# 4fader_main.net
KiCad netlist of a schematic drawn in Altium Designer
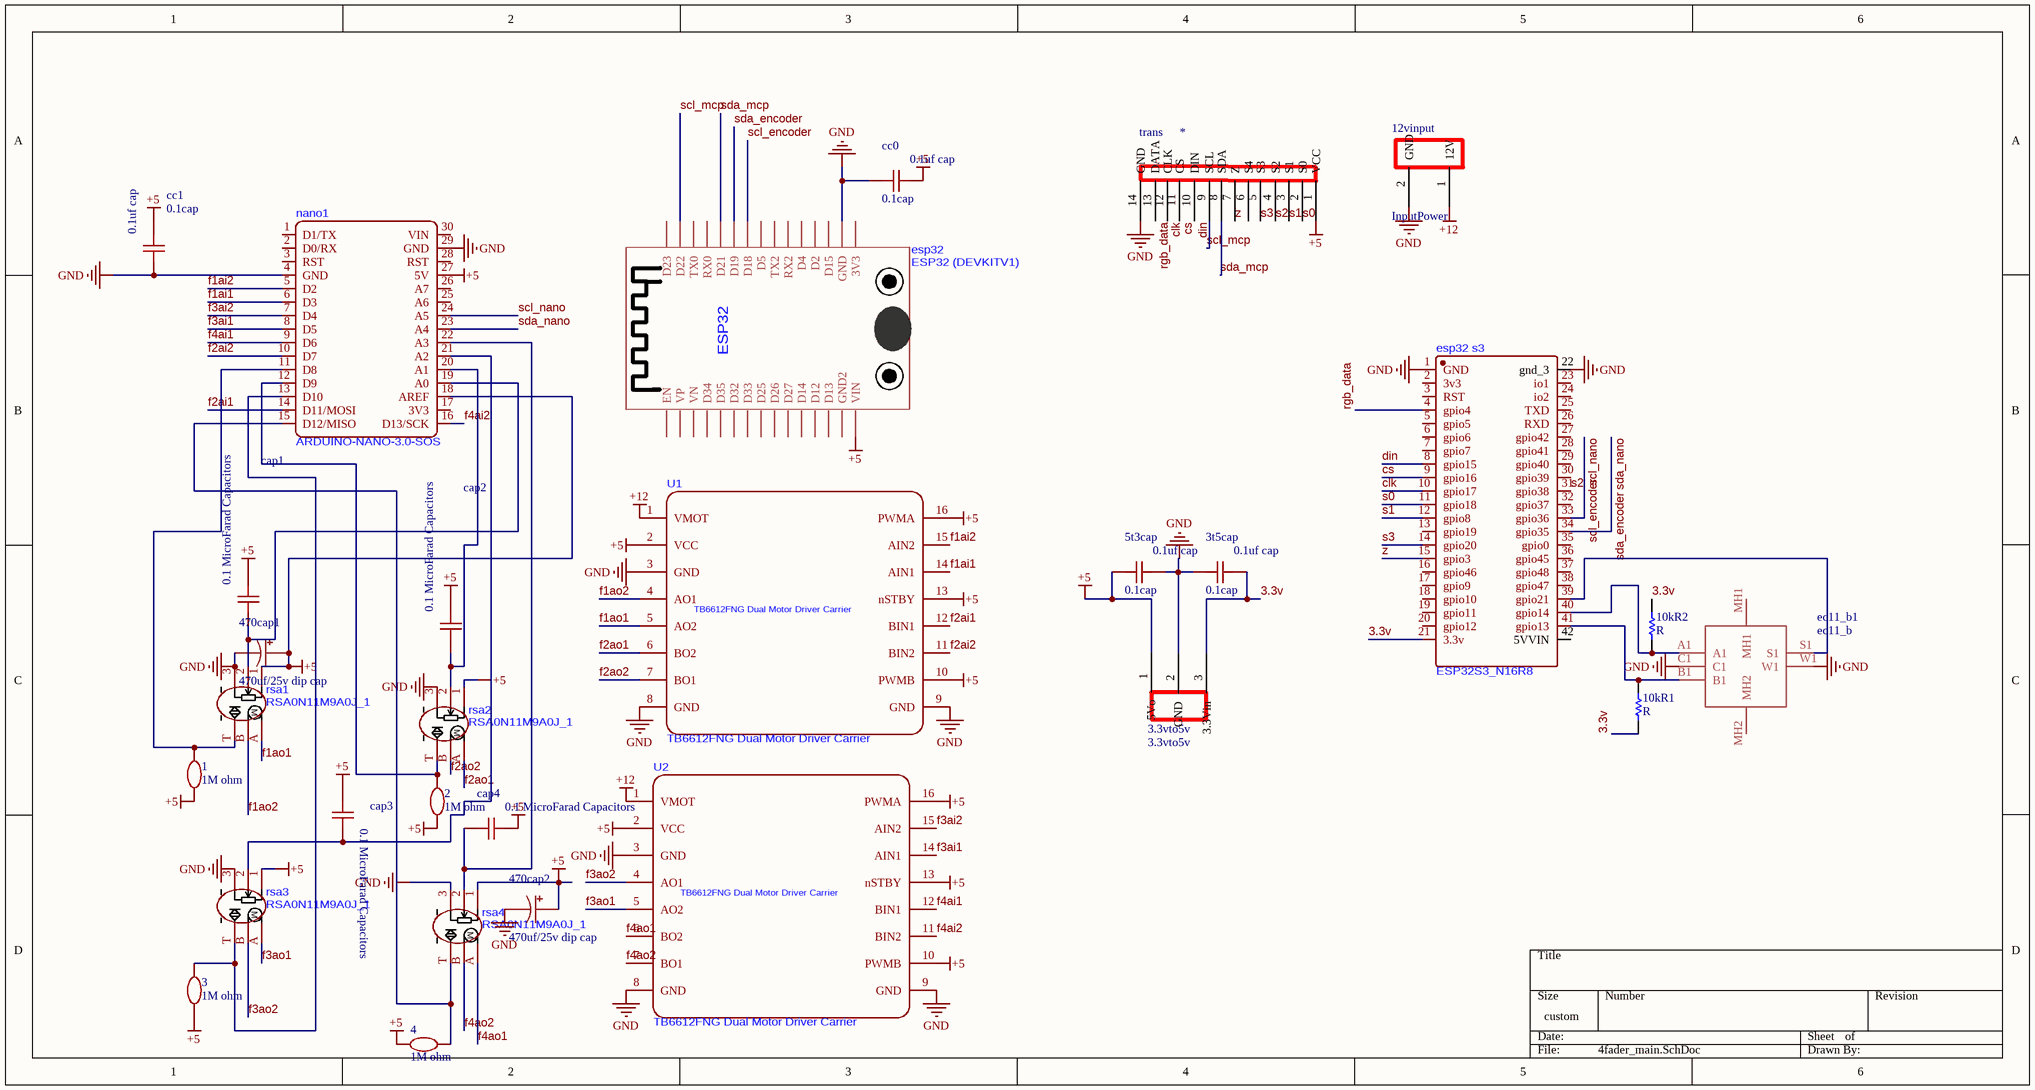
[diagram p0: 4fader_main.SchDoc]

(export (version "E")
  (design (tool "Eeschema 10.0.6"))
  (components
    (comp (ref "*")
      (value "trans")
      (footprint "FPC-SMD_KH-FG1.0-H2.0-14PIN")
      (libsource (lib "8_1") (part "trans"))
    )
    (comp (ref "1") (value "1M ohm") (footprint "ohms") (libsource (lib "8_1") (part "33k ohm")))
    (comp (ref "2") (value "1M ohm") (footprint "ohms") (libsource (lib "8_1") (part "33k ohm")))
    (comp (ref "3") (value "1M ohm") (footprint "ohms") (libsource (lib "8_1") (part "33k ohm")))
    (comp (ref "3.3vto5v")
      (value "3.3vto5v")
      (footprint "3.3vto5v")
      (libsource (lib "8_1") (part "3.3vto5v"))
    )
    (comp (ref "3t5cap") (value "0.1cap") (footprint "capcitor_1nf") (libsource (lib "8_1") (part "0.1cap")))
    (comp (ref "4") (value "1M ohm") (footprint "ohms") (libsource (lib "8_1") (part "33k ohm")))
    (comp (ref "5t3cap") (value "0.1cap") (footprint "capcitor_1nf") (libsource (lib "8_1") (part "0.1cap")))
    (comp (ref "10kR1")
      (value "R")
      (footprint "RESC2013X60X30LL20T20")
      (fields (field (name "MANUFACTURER") "KOA Speer") (field (name "PART NUMBER") "SG73S2ATTD1101F"))
      (libsource (lib "8_1") (part "CMP-2001-02660-1"))
    )
    (comp (ref "10kR2")
      (value "R")
      (footprint "RESC2013X60X30LL20T20")
      (fields (field (name "MANUFACTURER") "KOA Speer") (field (name "PART NUMBER") "SG73S2ATTD1101F"))
      (libsource (lib "8_1") (part "CMP-2001-02660-1"))
    )
    (comp (ref "12vinput")
      (value "InputPower")
      (footprint "InputPower")
      (libsource (lib "8_1") (part "InputPower"))
    )
    (comp (ref "470cap1")
      (value "470uf/25v dip cap")
      (footprint "470UF/25V-G1")
      (libsource (lib "8_1") (part "470uf/25v dip cap"))
    )
    (comp (ref "470cap2")
      (value "470uf/25v dip cap")
      (footprint "470UF/25V-G1")
      (libsource (lib "8_1") (part "470uf/25v dip cap"))
    )
    (comp (ref "cap1") (value "~") (footprint "capcitor_1nf") (libsource (lib "8_1") (part "0.1cap")))
    (comp (ref "cap2") (value "~") (footprint "capcitor_1nf") (libsource (lib "8_1") (part "0.1cap")))
    (comp (ref "cap3") (value "~") (footprint "capcitor_1nf") (libsource (lib "8_1") (part "0.1cap")))
    (comp (ref "cap4") (value "~") (footprint "capcitor_1nf") (libsource (lib "8_1") (part "0.1cap")))
    (comp (ref "cc0") (value "0.1cap") (footprint "capcitor_1nf") (libsource (lib "8_1") (part "0.1cap")))
    (comp (ref "cc1") (value "0.1cap") (footprint "capcitor_1nf") (libsource (lib "8_1") (part "0.1cap")))
    (comp (ref "ec11_b1") (value "ec11_b") (footprint "ec11_b") (libsource (lib "8_1") (part "ec11_b")))
    (comp (ref "esp32")
      (value "ESP32 (DEVKITV1)")
      (footprint "ESP32-DEVKITV1_ESP32-DEVKITV1")
      (libsource (lib "8_1") (part "ESP32 (DEVKITV1)"))
    )
    (comp (ref "esp32 s3")
      (value "ESP32S3_N16R8")
      (footprint "ESP32 S3 N16R8")
      (libsource (lib "8_1") (part "ESP32S3_N16R8"))
    )
    (comp (ref "nano1")
      (value "ARDUINO-NANO-3.0-SOS")
      (footprint "arduino_nano")
      (libsource (lib "8_1") (part "ARDUINO-NANO-3.0-SOS"))
    )
    (comp (ref "rsa1")
      (value "RSA0N11M9A0J_1")
      (footprint "RSA0N11M9A0J")
      (libsource (lib "8_1") (part "RSA0N11M9A0J_1"))
    )
    (comp (ref "rsa2")
      (value "RSA0N11M9A0J_1")
      (footprint "RSA0N11M9A0J")
      (libsource (lib "8_1") (part "RSA0N11M9A0J_1"))
    )
    (comp (ref "rsa3")
      (value "RSA0N11M9A0J_1")
      (footprint "RSA0N11M9A0J")
      (libsource (lib "8_1") (part "RSA0N11M9A0J_1"))
    )
    (comp (ref "rsa4")
      (value "RSA0N11M9A0J_1")
      (footprint "RSA0N11M9A0J")
      (libsource (lib "8_1") (part "RSA0N11M9A0J_1"))
    )
    (comp (ref "U1")
      (value "TB6612FNG Dual Motor Driver Carrier")
      (footprint "TB6612FNG")
      (libsource (lib "8_1") (part "TB6612FNG Dual Motor Driver Carrier"))
    )
    (comp (ref "U2")
      (value "TB6612FNG Dual Motor Driver Carrier")
      (footprint "TB6612FNG")
      (libsource (lib "8_1") (part "TB6612FNG Dual Motor Driver Carrier"))
    )
  )
  (nets
    (net (code "1") (name "+5") (class "Default")
      (node (ref "*") (pin "1") (pinfunction "VCC_1") (pintype "passive"))
      (node (ref "1") (pin "1") (pinfunction "1_1") (pintype "passive"))
      (node (ref "2") (pin "1") (pinfunction "1_1") (pintype "passive"))
      (node (ref "3") (pin "2") (pinfunction "2_2") (pintype "passive"))
      (node (ref "3.3vto5v") (pin "1") (pinfunction "5Vo_1") (pintype "passive"))
      (node (ref "4") (pin "2") (pinfunction "2_2") (pintype "passive"))
      (node (ref "470cap1") (pin "1") (pinfunction "1_1") (pintype "passive"))
      (node (ref "470cap2") (pin "1") (pinfunction "1_1") (pintype "passive"))
      (node (ref "5t3cap") (pin "1") (pinfunction "1_1") (pintype "passive"))
      (node (ref "U1") (pin "10") (pinfunction "PWMB_10") (pintype "passive"))
      (node (ref "U1") (pin "13") (pinfunction "nSTBY_13") (pintype "passive"))
      (node (ref "U1") (pin "16") (pinfunction "PWMA_16") (pintype "passive"))
      (node (ref "U1") (pin "2") (pinfunction "VCC_2") (pintype "passive"))
      (node (ref "U2") (pin "10") (pinfunction "PWMB_10") (pintype "passive"))
      (node (ref "U2") (pin "13") (pinfunction "nSTBY_13") (pintype "passive"))
      (node (ref "U2") (pin "16") (pinfunction "PWMA_16") (pintype "passive"))
      (node (ref "U2") (pin "2") (pinfunction "VCC_2") (pintype "passive"))
      (node (ref "cap1") (pin "2") (pinfunction "2_2") (pintype "passive"))
      (node (ref "cap2") (pin "2") (pinfunction "2_2") (pintype "passive"))
      (node (ref "cap3") (pin "1") (pinfunction "1_1") (pintype "passive"))
      (node (ref "cap4") (pin "2") (pinfunction "2_2") (pintype "passive"))
      (node (ref "cc0") (pin "2") (pinfunction "2_2") (pintype "passive"))
      (node (ref "cc1") (pin "2") (pinfunction "2_2") (pintype "passive"))
      (node (ref "esp32") (pin "VIN") (pinfunction "VIN_VIN") (pintype "passive"))
      (node (ref "nano1") (pin "18") (pinfunction "AREF_18") (pintype "passive"))
      (node (ref "nano1") (pin "27") (pinfunction "5V_27") (pintype "passive"))
      (node (ref "rsa1") (pin "1") (pinfunction "1_1") (pintype "passive"))
      (node (ref "rsa2") (pin "1") (pinfunction "1_1") (pintype "passive"))
      (node (ref "rsa3") (pin "1") (pinfunction "1_1") (pintype "passive"))
      (node (ref "rsa4") (pin "1") (pinfunction "1_1") (pintype "passive"))
    )
    (net (code "2") (name "+12") (class "Default")
      (node (ref "12vinput") (pin "1") (pinfunction "12V_1") (pintype "passive"))
      (node (ref "U1") (pin "1") (pinfunction "VMOT_1") (pintype "passive"))
      (node (ref "U2") (pin "1") (pinfunction "VMOT_1") (pintype "passive"))
    )
    (net (code "3") (name "/3.3v") (class "Default")
      (node (ref "10kR1") (pin "1") (pinfunction "1_1") (pintype "passive"))
      (node (ref "10kR2") (pin "2") (pinfunction "2_2") (pintype "passive"))
      (node (ref "3.3vto5v") (pin "3") (pinfunction "3.3Vin_3") (pintype "passive"))
      (node (ref "3t5cap") (pin "2") (pinfunction "2_2") (pintype "passive"))
      (node (ref "esp32 s3") (pin "21") (pinfunction "3.3v_21") (pintype "passive"))
    )
    (net (code "4") (name "/clk") (class "Default")
      (node (ref "*") (pin "12") (pinfunction "CLK_12") (pintype "passive"))
      (node (ref "esp32 s3") (pin "10") (pinfunction "gpio17_10") (pintype "passive"))
    )
    (net (code "5") (name "/cs") (class "Default")
      (node (ref "*") (pin "11") (pinfunction "CS_11") (pintype "passive"))
      (node (ref "esp32 s3") (pin "9") (pinfunction "gpio16_9") (pintype "passive"))
    )
    (net (code "6") (name "/din") (class "Default")
      (node (ref "*") (pin "10") (pinfunction "DIN_10") (pintype "passive"))
      (node (ref "esp32 s3") (pin "8") (pinfunction "gpio15_8") (pintype "passive"))
    )
    (net (code "7") (name "/f1ai1") (class "Default")
      (node (ref "U1") (pin "14") (pinfunction "AIN1_14") (pintype "passive"))
      (node (ref "nano1") (pin "6") (pinfunction "D3_6") (pintype "passive"))
    )
    (net (code "8") (name "/f1ai2") (class "Default")
      (node (ref "U1") (pin "15") (pinfunction "AIN2_15") (pintype "passive"))
      (node (ref "nano1") (pin "5") (pinfunction "D2_5") (pintype "passive"))
    )
    (net (code "9") (name "/f1ao1") (class "Default")
      (node (ref "U1") (pin "5") (pinfunction "AO2_5") (pintype "passive"))
      (node (ref "rsa1") (pin "A") (pinfunction "A_A") (pintype "passive"))
    )
    (net (code "10") (name "/f1ao2") (class "Default")
      (node (ref "U1") (pin "4") (pinfunction "AO1_4") (pintype "passive"))
      (node (ref "rsa1") (pin "B") (pinfunction "B_B") (pintype "passive"))
    )
    (net (code "11") (name "/f2ai1") (class "Default")
      (node (ref "U1") (pin "12") (pinfunction "BIN1_12") (pintype "passive"))
      (node (ref "nano1") (pin "14") (pinfunction "D11/MOSI_14") (pintype "passive"))
    )
    (net (code "12") (name "/f2ai2") (class "Default")
      (node (ref "U1") (pin "11") (pinfunction "BIN2_11") (pintype "passive"))
      (node (ref "nano1") (pin "10") (pinfunction "D7_10") (pintype "passive"))
    )
    (net (code "13") (name "/f2ao1") (class "Default")
      (node (ref "U1") (pin "6") (pinfunction "BO2_6") (pintype "passive"))
      (node (ref "rsa2") (pin "A") (pinfunction "A_A") (pintype "passive"))
    )
    (net (code "14") (name "/f2ao2") (class "Default")
      (node (ref "U1") (pin "7") (pinfunction "BO1_7") (pintype "passive"))
      (node (ref "rsa2") (pin "B") (pinfunction "B_B") (pintype "passive"))
    )
    (net (code "15") (name "/f3ai1") (class "Default")
      (node (ref "U2") (pin "14") (pinfunction "AIN1_14") (pintype "passive"))
      (node (ref "nano1") (pin "8") (pinfunction "D5_8") (pintype "passive"))
    )
    (net (code "16") (name "/f3ai2") (class "Default")
      (node (ref "U2") (pin "15") (pinfunction "AIN2_15") (pintype "passive"))
      (node (ref "nano1") (pin "7") (pinfunction "D4_7") (pintype "passive"))
    )
    (net (code "17") (name "/f3ao1") (class "Default")
      (node (ref "U2") (pin "5") (pinfunction "AO2_5") (pintype "passive"))
      (node (ref "rsa3") (pin "A") (pinfunction "A_A") (pintype "passive"))
    )
    (net (code "18") (name "/f3ao2") (class "Default")
      (node (ref "U2") (pin "4") (pinfunction "AO1_4") (pintype "passive"))
      (node (ref "rsa3") (pin "B") (pinfunction "B_B") (pintype "passive"))
    )
    (net (code "19") (name "/f4ai1") (class "Default")
      (node (ref "U2") (pin "12") (pinfunction "BIN1_12") (pintype "passive"))
      (node (ref "nano1") (pin "9") (pinfunction "D6_9") (pintype "passive"))
    )
    (net (code "20") (name "/f4ai2") (class "Default")
      (node (ref "U2") (pin "11") (pinfunction "BIN2_11") (pintype "passive"))
      (node (ref "nano1") (pin "16") (pinfunction "D13/SCK_16") (pintype "passive"))
    )
    (net (code "21") (name "/f4ao1") (class "Default")
      (node (ref "U2") (pin "6") (pinfunction "BO2_6") (pintype "passive"))
      (node (ref "rsa4") (pin "A") (pinfunction "A_A") (pintype "passive"))
    )
    (net (code "22") (name "/f4ao2") (class "Default")
      (node (ref "U2") (pin "7") (pinfunction "BO1_7") (pintype "passive"))
      (node (ref "rsa4") (pin "B") (pinfunction "B_B") (pintype "passive"))
    )
    (net (code "23") (name "/rgb_data") (class "Default")
      (node (ref "*") (pin "13") (pinfunction "DATA_13") (pintype "passive"))
      (node (ref "esp32 s3") (pin "4") (pinfunction "gpio4_4") (pintype "passive"))
    )
    (net (code "24") (name "/s0") (class "Default")
      (node (ref "*") (pin "2") (pinfunction "S0_2") (pintype "passive"))
      (node (ref "esp32 s3") (pin "11") (pinfunction "gpio18_11") (pintype "passive"))
    )
    (net (code "25") (name "/s1") (class "Default")
      (node (ref "*") (pin "3") (pinfunction "S1_3") (pintype "passive"))
      (node (ref "esp32 s3") (pin "12") (pinfunction "gpio8_12") (pintype "passive"))
    )
    (net (code "26") (name "/s2") (class "Default")
      (node (ref "*") (pin "4") (pinfunction "S2_4") (pintype "passive"))
      (node (ref "esp32 s3") (pin "31") (pinfunction "gpio38_31") (pintype "passive"))
    )
    (net (code "27") (name "/s3") (class "Default")
      (node (ref "*") (pin "5") (pinfunction "S3_5") (pintype "passive"))
      (node (ref "esp32 s3") (pin "14") (pinfunction "gpio20_14") (pintype "passive"))
    )
    (net (code "28") (name "/scl_encoder") (class "Default")
      (node (ref "esp32") (pin "D18") (pinfunction "D18_D18") (pintype "passive"))
      (node (ref "esp32 s3") (pin "33") (pinfunction "gpio36_33") (pintype "passive"))
      (node (ref "nano1") (pin "24") (pinfunction "A5_24") (pintype "passive"))
    )
    (net (code "29") (name "/scl_mcp") (class "Default")
      (node (ref "*") (pin "9") (pinfunction "SCL_9") (pintype "passive"))
      (node (ref "esp32") (pin "D22") (pinfunction "D22_D22") (pintype "passive"))
    )
    (net (code "30") (name "/sda_encoder") (class "Default")
      (node (ref "esp32") (pin "D19") (pinfunction "D19_D19") (pintype "passive"))
      (node (ref "esp32 s3") (pin "34") (pinfunction "gpio35_34") (pintype "passive"))
      (node (ref "nano1") (pin "23") (pinfunction "A4_23") (pintype "passive"))
    )
    (net (code "31") (name "/sda_mcp") (class "Default")
      (node (ref "*") (pin "8") (pinfunction "SDA_8") (pintype "passive"))
      (node (ref "esp32") (pin "D21") (pinfunction "D21_D21") (pintype "passive"))
    )
    (net (code "32") (name "/z") (class "Default")
      (node (ref "*") (pin "7") (pinfunction "Z_7") (pintype "passive"))
      (node (ref "esp32 s3") (pin "15") (pinfunction "gpio3_15") (pintype "passive"))
    )
    (net (code "33") (name "GND") (class "Default")
      (node (ref "*") (pin "14") (pinfunction "GND_14") (pintype "passive"))
      (node (ref "12vinput") (pin "2") (pinfunction "GND_2") (pintype "passive"))
      (node (ref "3.3vto5v") (pin "2") (pinfunction "GND_2") (pintype "passive"))
      (node (ref "3t5cap") (pin "1") (pinfunction "1_1") (pintype "passive"))
      (node (ref "470cap1") (pin "2") (pinfunction "2_2") (pintype "passive"))
      (node (ref "470cap2") (pin "2") (pinfunction "2_2") (pintype "passive"))
      (node (ref "5t3cap") (pin "2") (pinfunction "2_2") (pintype "passive"))
      (node (ref "U1") (pin "3") (pinfunction "GND_3") (pintype "passive"))
      (node (ref "U1") (pin "8") (pinfunction "GND_8") (pintype "passive"))
      (node (ref "U1") (pin "9") (pinfunction "GND_9") (pintype "passive"))
      (node (ref "U2") (pin "3") (pinfunction "GND_3") (pintype "passive"))
      (node (ref "U2") (pin "8") (pinfunction "GND_8") (pintype "passive"))
      (node (ref "U2") (pin "9") (pinfunction "GND_9") (pintype "passive"))
      (node (ref "cc0") (pin "1") (pinfunction "1_1") (pintype "passive"))
      (node (ref "cc1") (pin "1") (pinfunction "1_1") (pintype "passive"))
      (node (ref "ec11_b1") (pin "C1") (pinfunction "C1_C1") (pintype "passive"))
      (node (ref "ec11_b1") (pin "W1") (pinfunction "W1_W1") (pintype "passive"))
      (node (ref "esp32") (pin "GND") (pinfunction "GND_GND") (pintype "passive"))
      (node (ref "esp32 s3") (pin "1") (pinfunction "GND_1") (pintype "passive"))
      (node (ref "esp32 s3") (pin "22") (pinfunction "gnd_3_22") (pintype "passive"))
      (node (ref "nano1") (pin "29") (pinfunction "GND_29") (pintype "passive"))
      (node (ref "nano1") (pin "4") (pinfunction "GND_4") (pintype "passive"))
      (node (ref "rsa1") (pin "3") (pinfunction "3_3") (pintype "passive"))
      (node (ref "rsa2") (pin "3") (pinfunction "3_3") (pintype "passive"))
      (node (ref "rsa3") (pin "3") (pinfunction "3_3") (pintype "passive"))
      (node (ref "rsa4") (pin "3") (pinfunction "3_3") (pintype "passive"))
    )
    (net (code "34") (name "Net-(esp32 s3-gpio13)") (class "Default")
      (node (ref "10kR1") (pin "2") (pinfunction "2_2") (pintype "passive"))
      (node (ref "ec11_b1") (pin "B1") (pinfunction "B1_B1") (pintype "passive"))
      (node (ref "esp32 s3") (pin "41") (pinfunction "gpio13_41") (pintype "passive"))
    )
    (net (code "35") (name "Net-(esp32 s3-gpio14)") (class "Default")
      (node (ref "10kR2") (pin "1") (pinfunction "1_1") (pintype "passive"))
      (node (ref "ec11_b1") (pin "A1") (pinfunction "A1_A1") (pintype "passive"))
      (node (ref "esp32 s3") (pin "40") (pinfunction "gpio14_40") (pintype "passive"))
    )
    (net (code "36") (name "Net-(esp32 s3-gpio21)") (class "Default")
      (node (ref "ec11_b1") (pin "S1") (pinfunction "S1_S1") (pintype "passive"))
      (node (ref "esp32 s3") (pin "39") (pinfunction "gpio21_39") (pintype "passive"))
    )
    (net (code "37") (name "Net-(nano1-A0)") (class "Default")
      (node (ref "cap1") (pin "1") (pinfunction "1_1") (pintype "passive"))
      (node (ref "nano1") (pin "19") (pinfunction "A0_19") (pintype "passive"))
      (node (ref "rsa1") (pin "2") (pinfunction "w_2") (pintype "passive"))
    )
    (net (code "38") (name "Net-(nano1-A1)") (class "Default")
      (node (ref "cap2") (pin "1") (pinfunction "1_1") (pintype "passive"))
      (node (ref "nano1") (pin "20") (pinfunction "A1_20") (pintype "passive"))
      (node (ref "rsa2") (pin "2") (pinfunction "w_2") (pintype "passive"))
    )
    (net (code "39") (name "Net-(nano1-A2)") (class "Default")
      (node (ref "cap3") (pin "2") (pinfunction "2_2") (pintype "passive"))
      (node (ref "nano1") (pin "21") (pinfunction "A2_21") (pintype "passive"))
      (node (ref "rsa3") (pin "2") (pinfunction "w_2") (pintype "passive"))
    )
    (net (code "40") (name "Net-(nano1-A3)") (class "Default")
      (node (ref "cap4") (pin "1") (pinfunction "1_1") (pintype "passive"))
      (node (ref "nano1") (pin "22") (pinfunction "A3_22") (pintype "passive"))
      (node (ref "rsa4") (pin "2") (pinfunction "w_2") (pintype "passive"))
    )
    (net (code "41") (name "Net-(nano1-D8)") (class "Default")
      (node (ref "1") (pin "2") (pinfunction "2_2") (pintype "passive"))
      (node (ref "nano1") (pin "11") (pinfunction "D8_11") (pintype "passive"))
      (node (ref "rsa1") (pin "T") (pinfunction "T_T") (pintype "passive"))
    )
    (net (code "42") (name "Net-(nano1-D9)") (class "Default")
      (node (ref "2") (pin "2") (pinfunction "2_2") (pintype "passive"))
      (node (ref "nano1") (pin "12") (pinfunction "D9_12") (pintype "passive"))
      (node (ref "rsa2") (pin "T") (pinfunction "T_T") (pintype "passive"))
    )
    (net (code "43") (name "Net-(nano1-D10)") (class "Default")
      (node (ref "3") (pin "1") (pinfunction "1_1") (pintype "passive"))
      (node (ref "nano1") (pin "13") (pinfunction "D10_13") (pintype "passive"))
      (node (ref "rsa3") (pin "T") (pinfunction "T_T") (pintype "passive"))
    )
    (net (code "44") (name "Net-(nano1-D12{slash}MISO)") (class "Default")
      (node (ref "4") (pin "1") (pinfunction "1_1") (pintype "passive"))
      (node (ref "nano1") (pin "15") (pinfunction "D12/MISO_15") (pintype "passive"))
      (node (ref "rsa4") (pin "T") (pinfunction "T_T") (pintype "passive"))
    )
    (net (code "45") (name "unconnected-(*-S4-Pad6)") (class "Default")
      (node (ref "*") (pin "6") (pinfunction "S4_6") (pintype "passive"))
    )
    (net (code "46") (name "unconnected-(ec11_b1-PadMH1)") (class "Default")
      (node (ref "ec11_b1") (pin "MH1") (pinfunction "MH1_MH1") (pintype "passive"))
    )
    (net (code "47") (name "unconnected-(ec11_b1-PadMH2)") (class "Default")
      (node (ref "ec11_b1") (pin "MH2") (pinfunction "MH2_MH2") (pintype "passive"))
    )
    (net (code "48") (name "unconnected-(esp32 s3-3v3-Pad2)") (class "Default")
      (node (ref "esp32 s3") (pin "2") (pinfunction "3v3_2") (pintype "passive"))
    )
    (net (code "49") (name "unconnected-(esp32 s3-5VVIN-Pad42)") (class "Default")
      (node (ref "esp32 s3") (pin "42") (pinfunction "5VVIN_42") (pintype "passive"))
    )
    (net (code "50") (name "unconnected-(esp32 s3-RST-Pad3)") (class "Default")
      (node (ref "esp32 s3") (pin "3") (pinfunction "RST_3") (pintype "passive"))
    )
    (net (code "51") (name "unconnected-(esp32 s3-RXD-Pad26)") (class "Default")
      (node (ref "esp32 s3") (pin "26") (pinfunction "RXD_26") (pintype "passive"))
    )
    (net (code "52") (name "unconnected-(esp32 s3-TXD-Pad25)") (class "Default")
      (node (ref "esp32 s3") (pin "25") (pinfunction "TXD_25") (pintype "passive"))
    )
    (net (code "53") (name "unconnected-(esp32 s3-gpio0-Pad35)") (class "Default")
      (node (ref "esp32 s3") (pin "35") (pinfunction "gpio0_35") (pintype "passive"))
    )
    (net (code "54") (name "unconnected-(esp32 s3-gpio5-Pad5)") (class "Default")
      (node (ref "esp32 s3") (pin "5") (pinfunction "gpio5_5") (pintype "passive"))
    )
    (net (code "55") (name "unconnected-(esp32 s3-gpio6-Pad6)") (class "Default")
      (node (ref "esp32 s3") (pin "6") (pinfunction "gpio6_6") (pintype "passive"))
    )
    (net (code "56") (name "unconnected-(esp32 s3-gpio7-Pad7)") (class "Default")
      (node (ref "esp32 s3") (pin "7") (pinfunction "gpio7_7") (pintype "passive"))
    )
    (net (code "57") (name "unconnected-(esp32 s3-gpio9-Pad17)") (class "Default")
      (node (ref "esp32 s3") (pin "17") (pinfunction "gpio9_17") (pintype "passive"))
    )
    (net (code "58") (name "unconnected-(esp32 s3-gpio10-Pad18)") (class "Default")
      (node (ref "esp32 s3") (pin "18") (pinfunction "gpio10_18") (pintype "passive"))
    )
    (net (code "59") (name "unconnected-(esp32 s3-gpio11-Pad19)") (class "Default")
      (node (ref "esp32 s3") (pin "19") (pinfunction "gpio11_19") (pintype "passive"))
    )
    (net (code "60") (name "unconnected-(esp32 s3-gpio12-Pad20)") (class "Default")
      (node (ref "esp32 s3") (pin "20") (pinfunction "gpio12_20") (pintype "passive"))
    )
    (net (code "61") (name "unconnected-(esp32 s3-gpio19-Pad13)") (class "Default")
      (node (ref "esp32 s3") (pin "13") (pinfunction "gpio19_13") (pintype "passive"))
    )
    (net (code "62") (name "unconnected-(esp32 s3-gpio37-Pad32)") (class "Default")
      (node (ref "esp32 s3") (pin "32") (pinfunction "gpio37_32") (pintype "passive"))
    )
    (net (code "63") (name "unconnected-(esp32 s3-gpio39-Pad30)") (class "Default")
      (node (ref "esp32 s3") (pin "30") (pinfunction "gpio39_30") (pintype "passive"))
    )
    (net (code "64") (name "unconnected-(esp32 s3-gpio40-Pad29)") (class "Default")
      (node (ref "esp32 s3") (pin "29") (pinfunction "gpio40_29") (pintype "passive"))
    )
    (net (code "65") (name "unconnected-(esp32 s3-gpio41-Pad28)") (class "Default")
      (node (ref "esp32 s3") (pin "28") (pinfunction "gpio41_28") (pintype "passive"))
    )
    (net (code "66") (name "unconnected-(esp32 s3-gpio42-Pad27)") (class "Default")
      (node (ref "esp32 s3") (pin "27") (pinfunction "gpio42_27") (pintype "passive"))
    )
    (net (code "67") (name "unconnected-(esp32 s3-gpio45-Pad36)") (class "Default")
      (node (ref "esp32 s3") (pin "36") (pinfunction "gpio45_36") (pintype "passive"))
    )
    (net (code "68") (name "unconnected-(esp32 s3-gpio46-Pad16)") (class "Default")
      (node (ref "esp32 s3") (pin "16") (pinfunction "gpio46_16") (pintype "passive"))
    )
    (net (code "69") (name "unconnected-(esp32 s3-gpio47-Pad38)") (class "Default")
      (node (ref "esp32 s3") (pin "38") (pinfunction "gpio47_38") (pintype "passive"))
    )
    (net (code "70") (name "unconnected-(esp32 s3-gpio48-Pad37)") (class "Default")
      (node (ref "esp32 s3") (pin "37") (pinfunction "gpio48_37") (pintype "passive"))
    )
    (net (code "71") (name "unconnected-(esp32 s3-io1-Pad23)") (class "Default")
      (node (ref "esp32 s3") (pin "23") (pinfunction "io1_23") (pintype "passive"))
    )
    (net (code "72") (name "unconnected-(esp32 s3-io2-Pad24)") (class "Default")
      (node (ref "esp32 s3") (pin "24") (pinfunction "io2_24") (pintype "passive"))
    )
    (net (code "73") (name "unconnected-(esp32-Pad3V3)") (class "Default")
      (node (ref "esp32") (pin "3V3") (pinfunction "3V3_3V3") (pintype "passive"))
    )
    (net (code "74") (name "unconnected-(esp32-PadD2)") (class "Default")
      (node (ref "esp32") (pin "D2") (pinfunction "D2_D2") (pintype "passive"))
    )
    (net (code "75") (name "unconnected-(esp32-PadD4)") (class "Default")
      (node (ref "esp32") (pin "D4") (pinfunction "D4_D4") (pintype "passive"))
    )
    (net (code "76") (name "unconnected-(esp32-PadD5)") (class "Default")
      (node (ref "esp32") (pin "D5") (pinfunction "D5_D5") (pintype "passive"))
    )
    (net (code "77") (name "unconnected-(esp32-PadD12)") (class "Default")
      (node (ref "esp32") (pin "D12") (pinfunction "D12_D12") (pintype "passive"))
    )
    (net (code "78") (name "unconnected-(esp32-PadD13)") (class "Default")
      (node (ref "esp32") (pin "D13") (pinfunction "D13_D13") (pintype "passive"))
    )
    (net (code "79") (name "unconnected-(esp32-PadD14)") (class "Default")
      (node (ref "esp32") (pin "D14") (pinfunction "D14_D14") (pintype "passive"))
    )
    (net (code "80") (name "unconnected-(esp32-PadD15)") (class "Default")
      (node (ref "esp32") (pin "D15") (pinfunction "D15_D15") (pintype "passive"))
    )
    (net (code "81") (name "unconnected-(esp32-PadD23)") (class "Default")
      (node (ref "esp32") (pin "D23") (pinfunction "D23_D23") (pintype "passive"))
    )
    (net (code "82") (name "unconnected-(esp32-PadD25)") (class "Default")
      (node (ref "esp32") (pin "D25") (pinfunction "D25_D25") (pintype "passive"))
    )
    (net (code "83") (name "unconnected-(esp32-PadD26)") (class "Default")
      (node (ref "esp32") (pin "D26") (pinfunction "D26_D26") (pintype "passive"))
    )
    (net (code "84") (name "unconnected-(esp32-PadD27)") (class "Default")
      (node (ref "esp32") (pin "D27") (pinfunction "D27_D27") (pintype "passive"))
    )
    (net (code "85") (name "unconnected-(esp32-PadD32)") (class "Default")
      (node (ref "esp32") (pin "D32") (pinfunction "D32_D32") (pintype "passive"))
    )
    (net (code "86") (name "unconnected-(esp32-PadD33)") (class "Default")
      (node (ref "esp32") (pin "D33") (pinfunction "D33_D33") (pintype "passive"))
    )
    (net (code "87") (name "unconnected-(esp32-PadD34)") (class "Default")
      (node (ref "esp32") (pin "D34") (pinfunction "D34_D34") (pintype "passive"))
    )
    (net (code "88") (name "unconnected-(esp32-PadD35)") (class "Default")
      (node (ref "esp32") (pin "D35") (pinfunction "D35_D35") (pintype "passive"))
    )
    (net (code "89") (name "unconnected-(esp32-PadEN)") (class "Default")
      (node (ref "esp32") (pin "EN") (pinfunction "EN_EN") (pintype "passive"))
    )
    (net (code "90") (name "unconnected-(esp32-PadGND2)") (class "Default")
      (node (ref "esp32") (pin "GND2") (pinfunction "GND2_GND2") (pintype "passive"))
    )
    (net (code "91") (name "unconnected-(esp32-PadRX0)") (class "Default")
      (node (ref "esp32") (pin "RX0") (pinfunction "RX0_RX0") (pintype "passive"))
    )
    (net (code "92") (name "unconnected-(esp32-PadRX2)") (class "Default")
      (node (ref "esp32") (pin "RX2") (pinfunction "RX2_RX2") (pintype "passive"))
    )
    (net (code "93") (name "unconnected-(esp32-PadTX0)") (class "Default")
      (node (ref "esp32") (pin "TX0") (pinfunction "TX0_TX0") (pintype "passive"))
    )
    (net (code "94") (name "unconnected-(esp32-PadTX2)") (class "Default")
      (node (ref "esp32") (pin "TX2") (pinfunction "TX2_TX2") (pintype "passive"))
    )
    (net (code "95") (name "unconnected-(esp32-PadVN)") (class "Default")
      (node (ref "esp32") (pin "VN") (pinfunction "VN_VN") (pintype "passive"))
    )
    (net (code "96") (name "unconnected-(esp32-PadVP)") (class "Default")
      (node (ref "esp32") (pin "VP") (pinfunction "VP_VP") (pintype "passive"))
    )
    (net (code "97") (name "unconnected-(nano1-3V3-Pad17)") (class "Default")
      (node (ref "nano1") (pin "17") (pinfunction "3V3_17") (pintype "passive"))
    )
    (net (code "98") (name "unconnected-(nano1-A6-Pad25)") (class "Default")
      (node (ref "nano1") (pin "25") (pinfunction "A6_25") (pintype "passive"))
    )
    (net (code "99") (name "unconnected-(nano1-A7-Pad26)") (class "Default")
      (node (ref "nano1") (pin "26") (pinfunction "A7_26") (pintype "passive"))
    )
    (net (code "100") (name "unconnected-(nano1-D0{slash}RX-Pad2)") (class "Default")
      (node (ref "nano1") (pin "2") (pinfunction "D0/RX_2") (pintype "passive"))
    )
    (net (code "101") (name "unconnected-(nano1-D1{slash}TX-Pad1)") (class "Default")
      (node (ref "nano1") (pin "1") (pinfunction "D1/TX_1") (pintype "passive"))
    )
    (net (code "102") (name "unconnected-(nano1-RST-Pad3)") (class "Default")
      (node (ref "nano1") (pin "3") (pinfunction "RST_3") (pintype "passive"))
    )
    (net (code "103") (name "unconnected-(nano1-RST-Pad28)") (class "Default")
      (node (ref "nano1") (pin "28") (pinfunction "RST_28") (pintype "passive"))
    )
    (net (code "104") (name "unconnected-(nano1-VIN-Pad30)") (class "Default")
      (node (ref "nano1") (pin "30") (pinfunction "VIN_30") (pintype "passive"))
    )
  )
)
